# 2_P2.net
KiCad netlist of a schematic drawn in Altium Designer
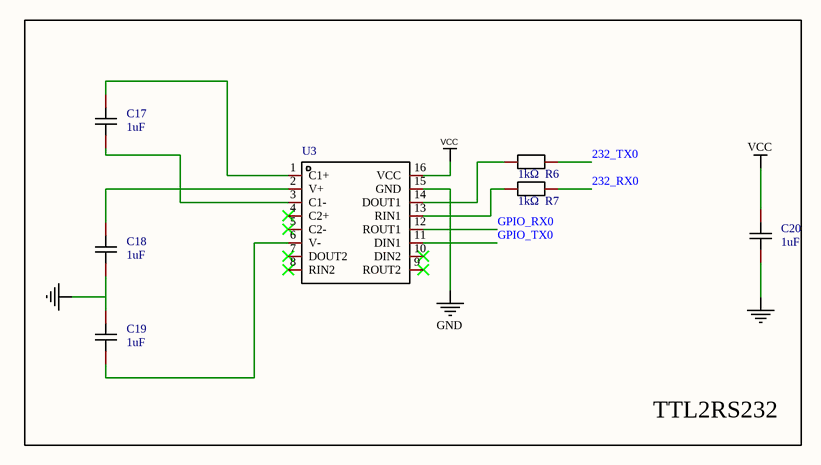
[diagram p0: 2_P2.schdoc]

(export (version "E")
  (design (tool "Eeschema 10.0.6"))
  (components
    (comp (ref "C17")
      (value "1uF")
      (description "容值:2.2uF;精度:±20%;额定电压:6.3V;材质(温度系数):X5R;")
      (fields
        (field (name "MANUFACTURER") "SAMSUNG(三星)")
        (field (name "MANUFACTURER PART") "CL05A225MQ5NNNC")
      )
      (libsource (lib "altium-import") (part "root_2_CL05A225MQ5NNNC_"))
    )
    (comp (ref "C18")
      (value "1uF")
      (description "容值:2.2uF;精度:±20%;额定电压:6.3V;材质(温度系数):X5R;")
      (fields
        (field (name "MANUFACTURER") "SAMSUNG(三星)")
        (field (name "MANUFACTURER PART") "CL05A225MQ5NNNC")
      )
      (libsource (lib "altium-import") (part "root_2_CL05A225MQ5NNNC_"))
    )
    (comp (ref "C19")
      (value "1uF")
      (description "容值:2.2uF;精度:±20%;额定电压:6.3V;材质(温度系数):X5R;")
      (fields
        (field (name "MANUFACTURER") "SAMSUNG(三星)")
        (field (name "MANUFACTURER PART") "CL05A225MQ5NNNC")
      )
      (libsource (lib "altium-import") (part "root_2_CL05A225MQ5NNNC_"))
    )
    (comp (ref "C20")
      (value "1uF")
      (description "容值:2.2uF;精度:±20%;额定电压:6.3V;材质(温度系数):X5R;")
      (fields
        (field (name "MANUFACTURER") "SAMSUNG(三星)")
        (field (name "MANUFACTURER PART") "CL05A225MQ5NNNC")
      )
      (libsource (lib "altium-import") (part "root_2_CL05A225MQ5NNNC_"))
    )
    (comp (ref "R6")
      (value "1kΩ")
      (description "阻值:1kΩ;精度:±5%;功率:63mW;温度系数:±100ppm/;")
      (fields
        (field (name "MANUFACTURER") "EVER OHMS(天二科技)")
        (field (name "MANUFACTURER PART") "CR0402J1K00Q10Z")
      )
      (libsource (lib "altium-import") (part "root_0_CR0402J1K00Q10Z_"))
    )
    (comp (ref "R7")
      (value "1kΩ")
      (description "阻值:1kΩ;精度:±5%;功率:63mW;温度系数:±100ppm/;")
      (fields
        (field (name "MANUFACTURER") "EVER OHMS(天二科技)")
        (field (name "MANUFACTURER PART") "CR0402J1K00Q10Z")
      )
      (libsource (lib "altium-import") (part "root_0_CR0402J1K00Q10Z_"))
    )
    (comp (ref "U3")
      (value "CBM3232AS16")
      (description "类型:-;协议类别:-;驱动器/接收器数:-;数据速率:-;")
      (fields (field (name "MANUFACTURER") "Corebai(芯佰微)"))
      (libsource (lib "altium-import") (part "root_0_CBM3232AS16_"))
    )
  )
  (nets
    (net (code "1") (name "/232_RX0") (class "Default")
      (node (ref "R7") (pin "2") (pinfunction "2_2") (pintype "passive"))
    )
    (net (code "2") (name "/232_TX0") (class "Default")
      (node (ref "R6") (pin "2") (pinfunction "2_2") (pintype "passive"))
    )
    (net (code "3") (name "/GPIO_RX0") (class "Default")
      (node (ref "U3") (pin "12") (pinfunction "ROUT1_12") (pintype "passive"))
    )
    (net (code "4") (name "/GPIO_TX0") (class "Default")
      (node (ref "U3") (pin "11") (pinfunction "DIN1_11") (pintype "passive"))
    )
    (net (code "5") (name "GND") (class "Default")
      (node (ref "C18") (pin "2") (pinfunction "2_2") (pintype "passive"))
      (node (ref "C19") (pin "1") (pinfunction "1_1") (pintype "passive"))
      (node (ref "C20") (pin "2") (pinfunction "2_2") (pintype "passive"))
      (node (ref "U3") (pin "15") (pinfunction "GND_15") (pintype "passive"))
    )
    (net (code "6") (name "Net-(U3-C1+)") (class "Default")
      (node (ref "C17") (pin "1") (pinfunction "1_1") (pintype "passive"))
      (node (ref "U3") (pin "1") (pinfunction "C1+_1") (pintype "passive"))
    )
    (net (code "7") (name "Net-(U3-C1-)") (class "Default")
      (node (ref "C17") (pin "2") (pinfunction "2_2") (pintype "passive"))
      (node (ref "U3") (pin "3") (pinfunction "C1-_3") (pintype "passive"))
    )
    (net (code "8") (name "Net-(U3-DOUT1)") (class "Default")
      (node (ref "R6") (pin "1") (pinfunction "1_1") (pintype "passive"))
      (node (ref "U3") (pin "14") (pinfunction "DOUT1_14") (pintype "passive"))
    )
    (net (code "9") (name "Net-(U3-RIN1)") (class "Default")
      (node (ref "R7") (pin "1") (pinfunction "1_1") (pintype "passive"))
      (node (ref "U3") (pin "13") (pinfunction "RIN1_13") (pintype "passive"))
    )
    (net (code "10") (name "Net-(U3-V+)") (class "Default")
      (node (ref "C18") (pin "1") (pinfunction "1_1") (pintype "passive"))
      (node (ref "U3") (pin "2") (pinfunction "V+_2") (pintype "passive"))
    )
    (net (code "11") (name "Net-(U3-V-)") (class "Default")
      (node (ref "C19") (pin "2") (pinfunction "2_2") (pintype "passive"))
      (node (ref "U3") (pin "6") (pinfunction "V-_6") (pintype "passive"))
    )
    (net (code "12") (name "VCC") (class "Default")
      (node (ref "C20") (pin "1") (pinfunction "1_1") (pintype "passive"))
      (node (ref "U3") (pin "16") (pinfunction "VCC_16") (pintype "passive"))
    )
    (net (code "13") (name "unconnected-(U3-C2+-Pad4)") (class "Default")
      (node (ref "U3") (pin "4") (pinfunction "C2+_4") (pintype "passive+no_connect"))
    )
    (net (code "14") (name "unconnected-(U3-C2--Pad5)") (class "Default")
      (node (ref "U3") (pin "5") (pinfunction "C2-_5") (pintype "passive+no_connect"))
    )
    (net (code "15") (name "unconnected-(U3-DIN2-Pad10)") (class "Default")
      (node (ref "U3") (pin "10") (pinfunction "DIN2_10") (pintype "passive+no_connect"))
    )
    (net (code "16") (name "unconnected-(U3-DOUT2-Pad7)") (class "Default")
      (node (ref "U3") (pin "7") (pinfunction "DOUT2_7") (pintype "passive+no_connect"))
    )
    (net (code "17") (name "unconnected-(U3-RIN2-Pad8)") (class "Default")
      (node (ref "U3") (pin "8") (pinfunction "RIN2_8") (pintype "passive+no_connect"))
    )
    (net (code "18") (name "unconnected-(U3-ROUT2-Pad9)") (class "Default")
      (node (ref "U3") (pin "9") (pinfunction "ROUT2_9") (pintype "passive+no_connect"))
    )
  )
)
